# 05_Optical_Heads.net
KiCad netlist of a schematic drawn in Altium Designer
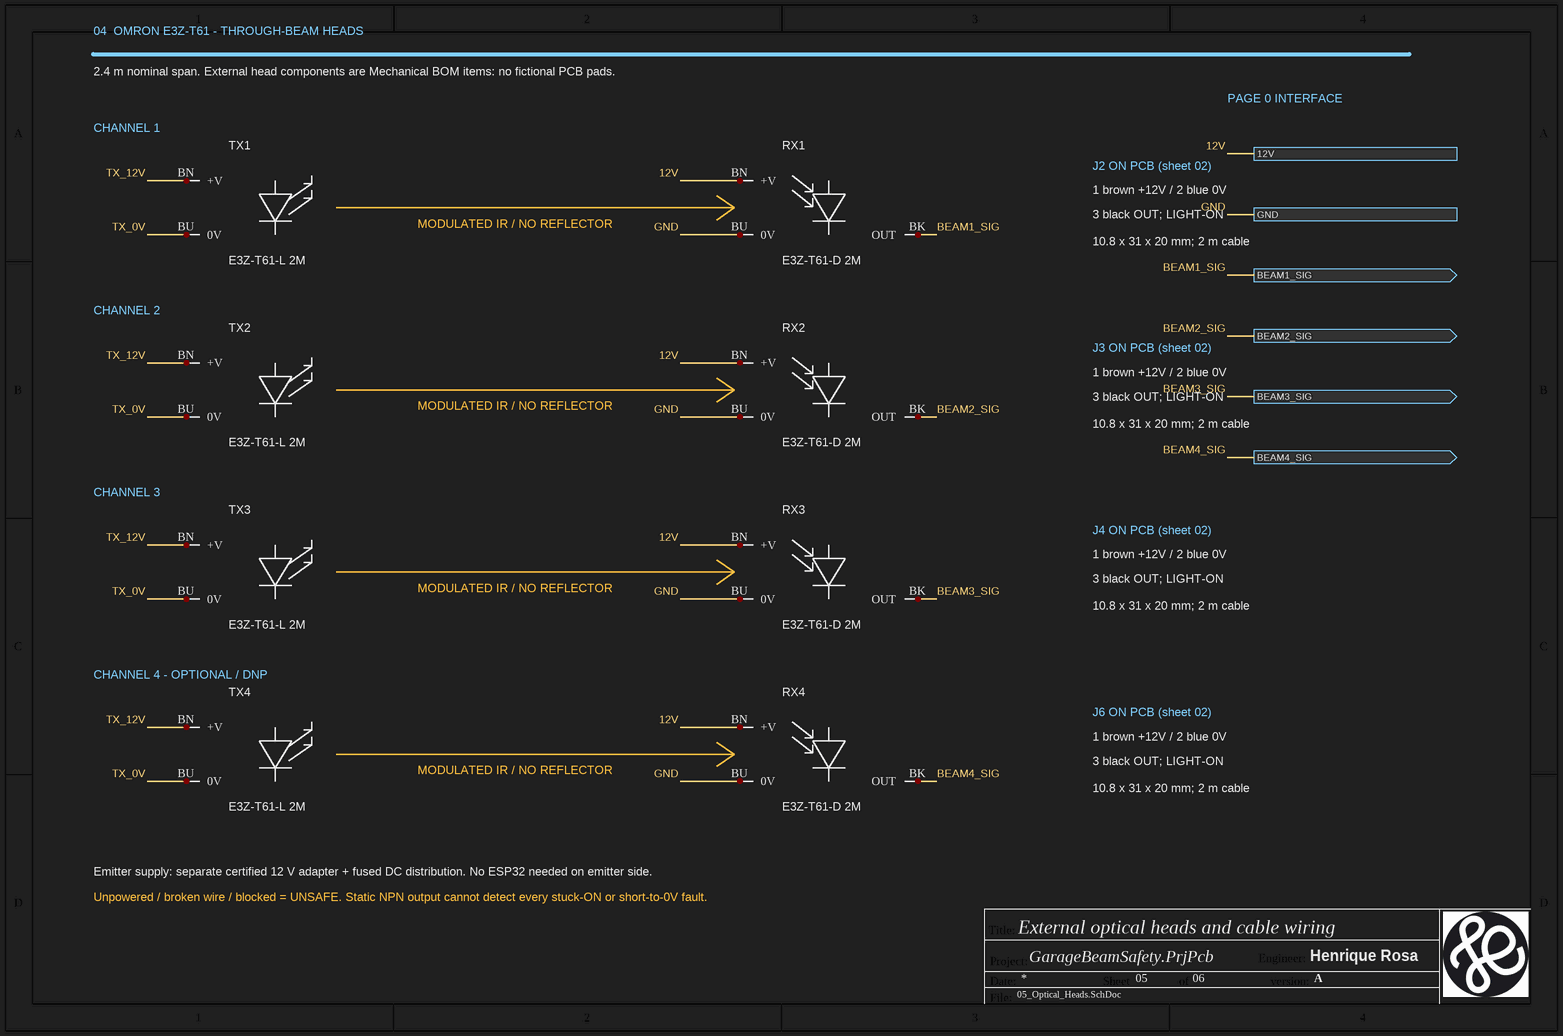
[diagram p0: 05_Optical_Heads.SchDoc]

(export (version "E")
  (design (tool "Eeschema 10.0.6"))
  (components
    (comp (ref "RX1")
      (value "E3Z-T61-D 2M")
      (description "RECEIVER / NPN LIGHT-ON; purchased in E3Z-T61 2M pair; frame-mounted, not PCB-mounted")
      (fields (field (name "MANUFACTURER") "Omron"))
      (libsource (lib "ReviewedComponents_20260912-233454") (part "E3Z-T61-D_2M__RX1_view"))
    )
    (comp (ref "RX2")
      (value "E3Z-T61-D 2M")
      (description "RECEIVER / NPN LIGHT-ON; purchased in E3Z-T61 2M pair; frame-mounted, not PCB-mounted")
      (fields (field (name "MANUFACTURER") "Omron"))
      (libsource (lib "ReviewedComponents_20260912-233454") (part "E3Z-T61-D_2M__RX2_view"))
    )
    (comp (ref "RX3")
      (value "E3Z-T61-D 2M")
      (description "RECEIVER / NPN LIGHT-ON; purchased in E3Z-T61 2M pair; frame-mounted, not PCB-mounted")
      (fields (field (name "MANUFACTURER") "Omron"))
      (libsource (lib "ReviewedComponents_20260912-233454") (part "E3Z-T61-D_2M__RX3_view"))
    )
    (comp (ref "RX4")
      (value "E3Z-T61-D 2M")
      (description "RECEIVER / NPN LIGHT-ON; purchased in E3Z-T61 2M pair; frame-mounted, not PCB-mounted")
      (fields (field (name "MANUFACTURER") "Omron"))
      (libsource (lib "ReviewedComponents_20260912-233454") (part "E3Z-T61-D_2M__RX4_view"))
    )
    (comp (ref "TX1")
      (value "E3Z-T61-L 2M")
      (description "EMITTER; purchased in E3Z-T61 2M pair; frame-mounted, not PCB-mounted")
      (fields (field (name "MANUFACTURER") "Omron"))
      (libsource (lib "ReviewedComponents_20260912-233454") (part "E3Z-T61-L_2M__TX1_view"))
    )
    (comp (ref "TX2")
      (value "E3Z-T61-L 2M")
      (description "EMITTER; purchased in E3Z-T61 2M pair; frame-mounted, not PCB-mounted")
      (fields (field (name "MANUFACTURER") "Omron"))
      (libsource (lib "ReviewedComponents_20260912-233454") (part "E3Z-T61-L_2M__TX2_view"))
    )
    (comp (ref "TX3")
      (value "E3Z-T61-L 2M")
      (description "EMITTER; purchased in E3Z-T61 2M pair; frame-mounted, not PCB-mounted")
      (fields (field (name "MANUFACTURER") "Omron"))
      (libsource (lib "ReviewedComponents_20260912-233454") (part "E3Z-T61-L_2M__TX3_view"))
    )
    (comp (ref "TX4")
      (value "E3Z-T61-L 2M")
      (description "EMITTER; purchased in E3Z-T61 2M pair; frame-mounted, not PCB-mounted")
      (fields (field (name "MANUFACTURER") "Omron"))
      (libsource (lib "ReviewedComponents_20260912-233454") (part "E3Z-T61-L_2M__TX4_view"))
    )
  )
  (nets
    (net (code "1") (name "/12V") (class "Default")
      (node (ref "RX1") (pin "BN") (pinfunction "+V_BN") (pintype "passive"))
      (node (ref "RX2") (pin "BN") (pinfunction "+V_BN") (pintype "passive"))
      (node (ref "RX3") (pin "BN") (pinfunction "+V_BN") (pintype "passive"))
      (node (ref "RX4") (pin "BN") (pinfunction "+V_BN") (pintype "passive"))
    )
    (net (code "2") (name "/BEAM1_SIG") (class "Default")
      (node (ref "RX1") (pin "BK") (pinfunction "OUT_BK") (pintype "passive"))
    )
    (net (code "3") (name "/BEAM2_SIG") (class "Default")
      (node (ref "RX2") (pin "BK") (pinfunction "OUT_BK") (pintype "passive"))
    )
    (net (code "4") (name "/BEAM3_SIG") (class "Default")
      (node (ref "RX3") (pin "BK") (pinfunction "OUT_BK") (pintype "passive"))
    )
    (net (code "5") (name "/BEAM4_SIG") (class "Default")
      (node (ref "RX4") (pin "BK") (pinfunction "OUT_BK") (pintype "passive"))
    )
    (net (code "6") (name "/GND") (class "Default")
      (node (ref "RX1") (pin "BU") (pinfunction "0V_BU") (pintype "passive"))
      (node (ref "RX2") (pin "BU") (pinfunction "0V_BU") (pintype "passive"))
      (node (ref "RX3") (pin "BU") (pinfunction "0V_BU") (pintype "passive"))
      (node (ref "RX4") (pin "BU") (pinfunction "0V_BU") (pintype "passive"))
    )
    (net (code "7") (name "/TX_0V") (class "Default")
      (node (ref "TX1") (pin "BU") (pinfunction "0V_BU") (pintype "passive"))
      (node (ref "TX2") (pin "BU") (pinfunction "0V_BU") (pintype "passive"))
      (node (ref "TX3") (pin "BU") (pinfunction "0V_BU") (pintype "passive"))
      (node (ref "TX4") (pin "BU") (pinfunction "0V_BU") (pintype "passive"))
    )
    (net (code "8") (name "/TX_12V") (class "Default")
      (node (ref "TX1") (pin "BN") (pinfunction "+V_BN") (pintype "passive"))
      (node (ref "TX2") (pin "BN") (pinfunction "+V_BN") (pintype "passive"))
      (node (ref "TX3") (pin "BN") (pinfunction "+V_BN") (pintype "passive"))
      (node (ref "TX4") (pin "BN") (pinfunction "+V_BN") (pintype "passive"))
    )
  )
)
